# Brakelight_V2.net
KiCad netlist of a schematic drawn in Altium Designer
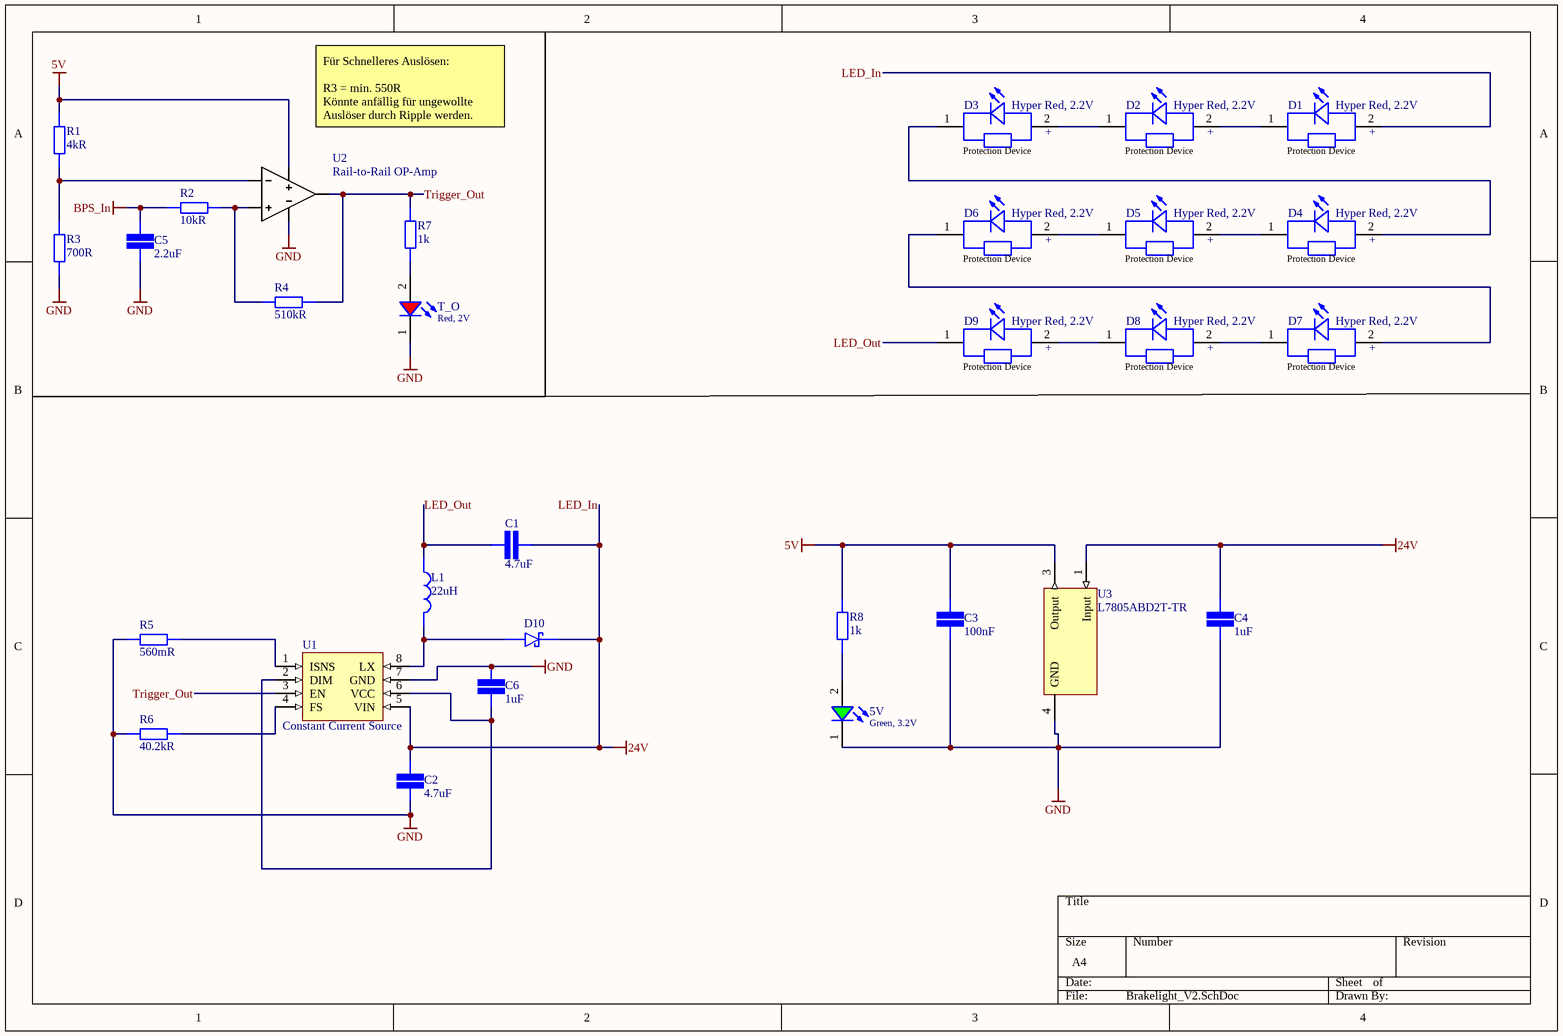
[diagram p0: Brakelight_V2.SchDoc]

(export (version "E")
  (design (tool "Eeschema 10.0.6"))
  (components
    (comp (ref "5V")
      (value "Green, 3.2V")
      (footprint "WL-SMCW_0603_H=0.7mm")
      (description "WL-SMCW SMT Mono-color Chip LED Waterclear, size 0603, Green, 3.2V, 140deg")
      (fields (field (name "PART NUMBER") "150060GS75000") (field (name "PUBLISHER") "Wurth Elektronik"))
      (libsource (lib "Altium_WL-SMCW (rev20a)") (part "150060GS75000"))
    )
    (comp (ref "C1")
      (value "4.7uF")
      (footprint "CAP 1206/3216")
      (description "Capacitor with multiple Footprints")
      (fields (field (name "VOLTAGE") "50V") (field (name "Comment") "SMD Capacitor 50V"))
      (libsource (lib "Standardbauteile") (part "SMD Capacitor"))
    )
    (comp (ref "C2")
      (value "4.7uF")
      (footprint "CAP 1206/3216")
      (description "Capacitor with multiple Footprints")
      (fields (field (name "VOLTAGE") "50V") (field (name "Comment") "SMD Capacitor 50V"))
      (libsource (lib "") (part "SMD Capacitor_2"))
    )
    (comp (ref "C3")
      (value "100nF")
      (footprint "CAP 0603/1608")
      (description "Capacitor with multiple Footprints")
      (fields (field (name "VOLTAGE") "16V") (field (name "Comment") "SMD Capacitor 6.3V"))
      (libsource (lib "") (part "SMD Capacitor_1"))
    )
    (comp (ref "C4")
      (value "1uF")
      (footprint "CAP 0603/1608")
      (description "Capacitor with multiple Footprints")
      (fields (field (name "VOLTAGE") "25V") (field (name "Comment") "SMD Capacitor 25V"))
      (libsource (lib "") (part "SMD Capacitor_1"))
    )
    (comp (ref "C5")
      (value "2.2uF")
      (footprint "CAP 0603/1608")
      (description "Capacitor with multiple Footprints")
      (fields (field (name "VOLTAGE") "6.3V") (field (name "Comment") "SMD Capacitor 6.3V"))
      (libsource (lib "") (part "SMD Capacitor_2"))
    )
    (comp (ref "C6")
      (value "1uF")
      (footprint "CAP 0603/1608")
      (description "Capacitor with multiple Footprints")
      (fields (field (name "Comment") "SMD Capacitor 10V"))
      (libsource (lib "") (part "SMD Capacitor_2"))
    )
    (comp (ref "D1")
      (value "Hyper Red, 2.2V")
      (footprint "WL-SMDC_3535")
      (description "WL-SMDC Horticulture SMT Monocolor Ceramic LED Waterclear, size 3535, 2.2V, Hyper Red")
      (fields
        (field (name "MANUFACTURER PART NUMBER") "150353HS74500")
        (field (name "MANUFACTURER") "Wurth Elektronik")
      )
      (libsource (lib "Altium_WL-SMDC (rev20a)") (part "150353HS74500"))
    )
    (comp (ref "D2")
      (value "Hyper Red, 2.2V")
      (footprint "WL-SMDC_3535")
      (description "WL-SMDC Horticulture SMT Monocolor Ceramic LED Waterclear, size 3535, 2.2V, Hyper Red")
      (fields
        (field (name "MANUFACTURER PART NUMBER") "150353HS74500")
        (field (name "MANUFACTURER") "Wurth Elektronik")
      )
      (libsource (lib "Altium_WL-SMDC (rev20a)") (part "150353HS74500"))
    )
    (comp (ref "D3")
      (value "Hyper Red, 2.2V")
      (footprint "WL-SMDC_3535")
      (description "WL-SMDC Horticulture SMT Monocolor Ceramic LED Waterclear, size 3535, 2.2V, Hyper Red")
      (fields
        (field (name "MANUFACTURER PART NUMBER") "150353HS74500")
        (field (name "MANUFACTURER") "Wurth Elektronik")
      )
      (libsource (lib "Altium_WL-SMDC (rev20a)") (part "150353HS74500"))
    )
    (comp (ref "D4")
      (value "Hyper Red, 2.2V")
      (footprint "WL-SMDC_3535")
      (description "WL-SMDC Horticulture SMT Monocolor Ceramic LED Waterclear, size 3535, 2.2V, Hyper Red")
      (fields
        (field (name "MANUFACTURER PART NUMBER") "150353HS74500")
        (field (name "MANUFACTURER") "Wurth Elektronik")
      )
      (libsource (lib "Altium_WL-SMDC (rev20a)") (part "150353HS74500"))
    )
    (comp (ref "D5")
      (value "Hyper Red, 2.2V")
      (footprint "WL-SMDC_3535")
      (description "WL-SMDC Horticulture SMT Monocolor Ceramic LED Waterclear, size 3535, 2.2V, Hyper Red")
      (fields
        (field (name "MANUFACTURER PART NUMBER") "150353HS74500")
        (field (name "MANUFACTURER") "Wurth Elektronik")
      )
      (libsource (lib "Altium_WL-SMDC (rev20a)") (part "150353HS74500"))
    )
    (comp (ref "D6")
      (value "Hyper Red, 2.2V")
      (footprint "WL-SMDC_3535")
      (description "WL-SMDC Horticulture SMT Monocolor Ceramic LED Waterclear, size 3535, 2.2V, Hyper Red")
      (fields
        (field (name "MANUFACTURER PART NUMBER") "150353HS74500")
        (field (name "MANUFACTURER") "Wurth Elektronik")
      )
      (libsource (lib "Altium_WL-SMDC (rev20a)") (part "150353HS74500"))
    )
    (comp (ref "D7")
      (value "Hyper Red, 2.2V")
      (footprint "WL-SMDC_3535")
      (description "WL-SMDC Horticulture SMT Monocolor Ceramic LED Waterclear, size 3535, 2.2V, Hyper Red")
      (fields
        (field (name "MANUFACTURER PART NUMBER") "150353HS74500")
        (field (name "MANUFACTURER") "Wurth Elektronik")
      )
      (libsource (lib "Altium_WL-SMDC (rev20a)") (part "150353HS74500"))
    )
    (comp (ref "D8")
      (value "Hyper Red, 2.2V")
      (footprint "WL-SMDC_3535")
      (description "WL-SMDC Horticulture SMT Monocolor Ceramic LED Waterclear, size 3535, 2.2V, Hyper Red")
      (fields
        (field (name "MANUFACTURER PART NUMBER") "150353HS74500")
        (field (name "MANUFACTURER") "Wurth Elektronik")
      )
      (libsource (lib "Altium_WL-SMDC (rev20a)") (part "150353HS74500"))
    )
    (comp (ref "D9")
      (value "Hyper Red, 2.2V")
      (footprint "WL-SMDC_3535")
      (description "WL-SMDC Horticulture SMT Monocolor Ceramic LED Waterclear, size 3535, 2.2V, Hyper Red")
      (fields
        (field (name "MANUFACTURER PART NUMBER") "150353HS74500")
        (field (name "MANUFACTURER") "Wurth Elektronik")
      )
      (libsource (lib "Altium_WL-SMDC (rev20a)") (part "150353HS74500"))
    )
    (comp (ref "D10")
      (value "Shottky Diode")
      (footprint "SODFL127P600-8N")
      (description "Surface-Mount Schottky Barrier Rectifier\r\n40V, 1A")
      (libsource (lib "libNico") (part "SS1FL4HM3/H"))
    )
    (comp (ref "L1")
      (value "22uH")
      (footprint "CHIP_1210_3225")
      (description "Ind Chip High Current Unshielded Wirewound 22uH 20% 100kHz Ferrite 780mA 1210 T/R")
      (fields (field (name "Comment") "SMD Inductor"))
      (libsource (lib "libNico") (part "L1210R220MDWIT"))
    )
    (comp (ref "R1")
      (value "4kR")
      (footprint "STACKPOLE CSR0603")
      (description "Resistor with multiple footprints")
      (fields (field (name "Comment") "SMD Resistor"))
      (libsource (lib "Standardbauteile") (part "SMD Resistor"))
    )
    (comp (ref "R2")
      (value "10kR")
      (footprint "STACKPOLE CSR0603")
      (description "Resistor with multiple footprints")
      (fields (field (name "Comment") "SMD Resistor"))
      (libsource (lib "Standardbauteile") (part "SMD Resistor"))
    )
    (comp (ref "R3")
      (value "700R")
      (footprint "STACKPOLE CSR0603")
      (description "Resistor with multiple footprints")
      (fields (field (name "Comment") "SMD Resistor"))
      (libsource (lib "Standardbauteile") (part "SMD Resistor"))
    )
    (comp (ref "R4")
      (value "510kR")
      (footprint "STACKPOLE CSR0603")
      (description "Resistor with multiple footprints")
      (fields (field (name "Comment") "SMD Resistor"))
      (libsource (lib "Standardbauteile") (part "SMD Resistor"))
    )
    (comp (ref "R5")
      (value "560mR")
      (footprint "STACKPOLE CSR0805")
      (description "Resistor with multiple footprints")
      (fields (field (name "POWER") "0.25") (field (name "Comment") "SMD Resistor 1/4W"))
      (libsource (lib "Standardbauteile") (part "SMD Resistor"))
    )
    (comp (ref "R6")
      (value "40.2kR")
      (footprint "STACKPOLE CSR0603")
      (description "Resistor with multiple footprints")
      (fields (field (name "Comment") "SMD Resistor"))
      (libsource (lib "Standardbauteile") (part "SMD Resistor"))
    )
    (comp (ref "R7")
      (value "1k")
      (footprint "STACKPOLE CSR0603")
      (description "Resistor with multiple footprints")
      (fields (field (name "Comment") "SMD Resistor"))
      (libsource (lib "Standardbauteile") (part "SMD Resistor"))
    )
    (comp (ref "R8")
      (value "1k")
      (footprint "STACKPOLE CSR0603")
      (description "Resistor with multiple footprints")
      (fields (field (name "Comment") "SMD Resistor"))
      (libsource (lib "Standardbauteile") (part "SMD Resistor"))
    )
    (comp (ref "T_O")
      (value "Red, 2V")
      (footprint "WL-SMCW_0603_H=0.7mm")
      (description "WL-SMCW SMT Mono-color Chip LED Waterclear, size 0603, Red, 2V, 140deg")
      (fields (field (name "PART NUMBER") "150060RS75000") (field (name "PUBLISHER") "Wurth Elektronik"))
      (libsource (lib "Altium_WL-SMCW (rev20a)") (part "150060RS75000"))
    )
    (comp (ref "U1")
      (value "Constant Current Source")
      (footprint "TSOP65P490X110_HS-9M")
      (description "LM3407 350-mA, Constant Current Output Floating Buck Switching Converter\r\nfor High-Power LEDs")
      (libsource (lib "libNico") (part "LM3407MYX/NOPB"))
    )
    (comp (ref "U2")
      (value "Rail-to-Rail OP-Amp")
      (footprint "5-Lead_SOT_SC-70")
      (description "MCP6231 Series 6 V 300 kHz Rail-to-Rail I/O Operational Amplifier - SC-70-5")
      (libsource (lib "libNico") (part "MCP6231UT-E/LT"))
    )
    (comp (ref "U3")
      (value "L7805ABD2T-TR")
      (footprint "DPAK254P1542X460-3M")
      (description "Linear Voltage Regulators 5.0V 1.5A Positive")
      (libsource (lib "LibJulian") (part "L7805ABD2T-TR"))
    )
  )
  (nets
    (net (code "1") (name "/LED_Out") (class "Default")
      (node (ref "C1") (pin "2") (pinfunction "2_2") (pintype "passive"))
      (node (ref "D9") (pin "1") (pinfunction "K_1") (pintype "passive"))
      (node (ref "L1") (pin "1") (pinfunction "1_1") (pintype "passive"))
    )
    (net (code "2") (name "/Trigger_Out") (class "Default")
      (node (ref "R4") (pin "1") (pinfunction "1_1") (pintype "passive"))
      (node (ref "R7") (pin "1") (pinfunction "1_1") (pintype "passive"))
      (node (ref "U1") (pin "3") (pinfunction "EN_3") (pintype "input"))
      (node (ref "U2") (pin "4") (pinfunction "Vout_4") (pintype "passive"))
    )
    (net (code "3") (name "5V") (class "Default")
      (node (ref "C3") (pin "1") (pinfunction "1_1") (pintype "passive"))
      (node (ref "R1") (pin "2") (pinfunction "2_2") (pintype "passive"))
      (node (ref "R8") (pin "2") (pinfunction "2_2") (pintype "passive"))
      (node (ref "U2") (pin "5") (pinfunction "VDD_5") (pintype "passive"))
      (node (ref "U3") (pin "3") (pinfunction "Output_3") (pintype "output"))
    )
    (net (code "4") (name "24V") (class "Default")
      (node (ref "C1") (pin "1") (pinfunction "1_1") (pintype "passive"))
      (node (ref "C2") (pin "2") (pinfunction "2_2") (pintype "passive"))
      (node (ref "C4") (pin "1") (pinfunction "1_1") (pintype "passive"))
      (node (ref "D1") (pin "2") (pinfunction "A_2") (pintype "passive"))
      (node (ref "D10") (pin "1C") (pinfunction "C_1C") (pintype "passive"))
      (node (ref "U1") (pin "5") (pinfunction "VIN_5") (pintype "input"))
      (node (ref "U3") (pin "1") (pinfunction "Input_1") (pintype "input"))
    )
    (net (code "5") (name "BPS_In") (class "Default")
      (node (ref "C5") (pin "2") (pinfunction "2_2") (pintype "passive"))
      (node (ref "R2") (pin "2") (pinfunction "2_2") (pintype "passive"))
    )
    (net (code "6") (name "GND") (class "Default")
      (node (ref "5V") (pin "1") (pinfunction "K_1") (pintype "passive"))
      (node (ref "C2") (pin "1") (pinfunction "1_1") (pintype "passive"))
      (node (ref "C3") (pin "2") (pinfunction "2_2") (pintype "passive"))
      (node (ref "C4") (pin "2") (pinfunction "2_2") (pintype "passive"))
      (node (ref "C5") (pin "1") (pinfunction "1_1") (pintype "passive"))
      (node (ref "C6") (pin "2") (pinfunction "2_2") (pintype "passive"))
      (node (ref "R3") (pin "1") (pinfunction "1_1") (pintype "passive"))
      (node (ref "R5") (pin "2") (pinfunction "2_2") (pintype "passive"))
      (node (ref "R6") (pin "2") (pinfunction "2_2") (pintype "passive"))
      (node (ref "T_O") (pin "1") (pinfunction "K_1") (pintype "passive"))
      (node (ref "U1") (pin "7") (pinfunction "GND_7") (pintype "input"))
      (node (ref "U2") (pin "2") (pinfunction "VSS_2") (pintype "passive"))
      (node (ref "U3") (pin "4") (pinfunction "GND_4") (pintype "passive"))
    )
    (net (code "7") (name "Net-(5V-A)") (class "Default")
      (node (ref "5V") (pin "2") (pinfunction "A_2") (pintype "passive"))
      (node (ref "R8") (pin "1") (pinfunction "1_1") (pintype "passive"))
    )
    (net (code "8") (name "Net-(D1-K)") (class "Default")
      (node (ref "D1") (pin "1") (pinfunction "K_1") (pintype "passive"))
      (node (ref "D2") (pin "2") (pinfunction "A_2") (pintype "passive"))
    )
    (net (code "9") (name "Net-(D2-K)") (class "Default")
      (node (ref "D2") (pin "1") (pinfunction "K_1") (pintype "passive"))
      (node (ref "D3") (pin "2") (pinfunction "A_2") (pintype "passive"))
    )
    (net (code "10") (name "Net-(D3-K)") (class "Default")
      (node (ref "D3") (pin "1") (pinfunction "K_1") (pintype "passive"))
      (node (ref "D4") (pin "2") (pinfunction "A_2") (pintype "passive"))
    )
    (net (code "11") (name "Net-(D4-K)") (class "Default")
      (node (ref "D4") (pin "1") (pinfunction "K_1") (pintype "passive"))
      (node (ref "D5") (pin "2") (pinfunction "A_2") (pintype "passive"))
    )
    (net (code "12") (name "Net-(D5-K)") (class "Default")
      (node (ref "D5") (pin "1") (pinfunction "K_1") (pintype "passive"))
      (node (ref "D6") (pin "2") (pinfunction "A_2") (pintype "passive"))
    )
    (net (code "13") (name "Net-(D6-K)") (class "Default")
      (node (ref "D6") (pin "1") (pinfunction "K_1") (pintype "passive"))
      (node (ref "D7") (pin "2") (pinfunction "A_2") (pintype "passive"))
    )
    (net (code "14") (name "Net-(D7-K)") (class "Default")
      (node (ref "D7") (pin "1") (pinfunction "K_1") (pintype "passive"))
      (node (ref "D8") (pin "2") (pinfunction "A_2") (pintype "passive"))
    )
    (net (code "15") (name "Net-(D8-K)") (class "Default")
      (node (ref "D8") (pin "1") (pinfunction "K_1") (pintype "passive"))
      (node (ref "D9") (pin "2") (pinfunction "A_2") (pintype "passive"))
    )
    (net (code "16") (name "Net-(D10-A)") (class "Default")
      (node (ref "D10") (pin "2A") (pinfunction "A_2A") (pintype "passive"))
      (node (ref "L1") (pin "2") (pinfunction "2_2") (pintype "passive"))
      (node (ref "U1") (pin "8") (pinfunction "LX_8") (pintype "input"))
    )
    (net (code "17") (name "Net-(T_O-A)") (class "Default")
      (node (ref "R7") (pin "2") (pinfunction "2_2") (pintype "passive"))
      (node (ref "T_O") (pin "2") (pinfunction "A_2") (pintype "passive"))
    )
    (net (code "18") (name "Net-(U1-DIM)") (class "Default")
      (node (ref "C6") (pin "1") (pinfunction "1_1") (pintype "passive"))
      (node (ref "U1") (pin "2") (pinfunction "DIM_2") (pintype "input"))
      (node (ref "U1") (pin "6") (pinfunction "VCC_6") (pintype "input"))
    )
    (net (code "19") (name "Net-(U1-FS)") (class "Default")
      (node (ref "R6") (pin "1") (pinfunction "1_1") (pintype "passive"))
      (node (ref "U1") (pin "4") (pinfunction "FS_4") (pintype "input"))
    )
    (net (code "20") (name "Net-(U1-ISNS)") (class "Default")
      (node (ref "R5") (pin "1") (pinfunction "1_1") (pintype "passive"))
      (node (ref "U1") (pin "1") (pinfunction "ISNS_1") (pintype "input"))
    )
    (net (code "21") (name "Net-(U2-Vin+)") (class "Default")
      (node (ref "R2") (pin "1") (pinfunction "1_1") (pintype "passive"))
      (node (ref "R4") (pin "2") (pinfunction "2_2") (pintype "passive"))
      (node (ref "U2") (pin "1") (pinfunction "Vin+_1") (pintype "passive"))
    )
    (net (code "22") (name "Net-(U2-Vin-)") (class "Default")
      (node (ref "R1") (pin "1") (pinfunction "1_1") (pintype "passive"))
      (node (ref "R3") (pin "2") (pinfunction "2_2") (pintype "passive"))
      (node (ref "U2") (pin "3") (pinfunction "Vin-_3") (pintype "passive"))
    )
  )
)
